# Mainsnode_v2_wifi.net
KiCad netlist of a schematic drawn in EAGLE
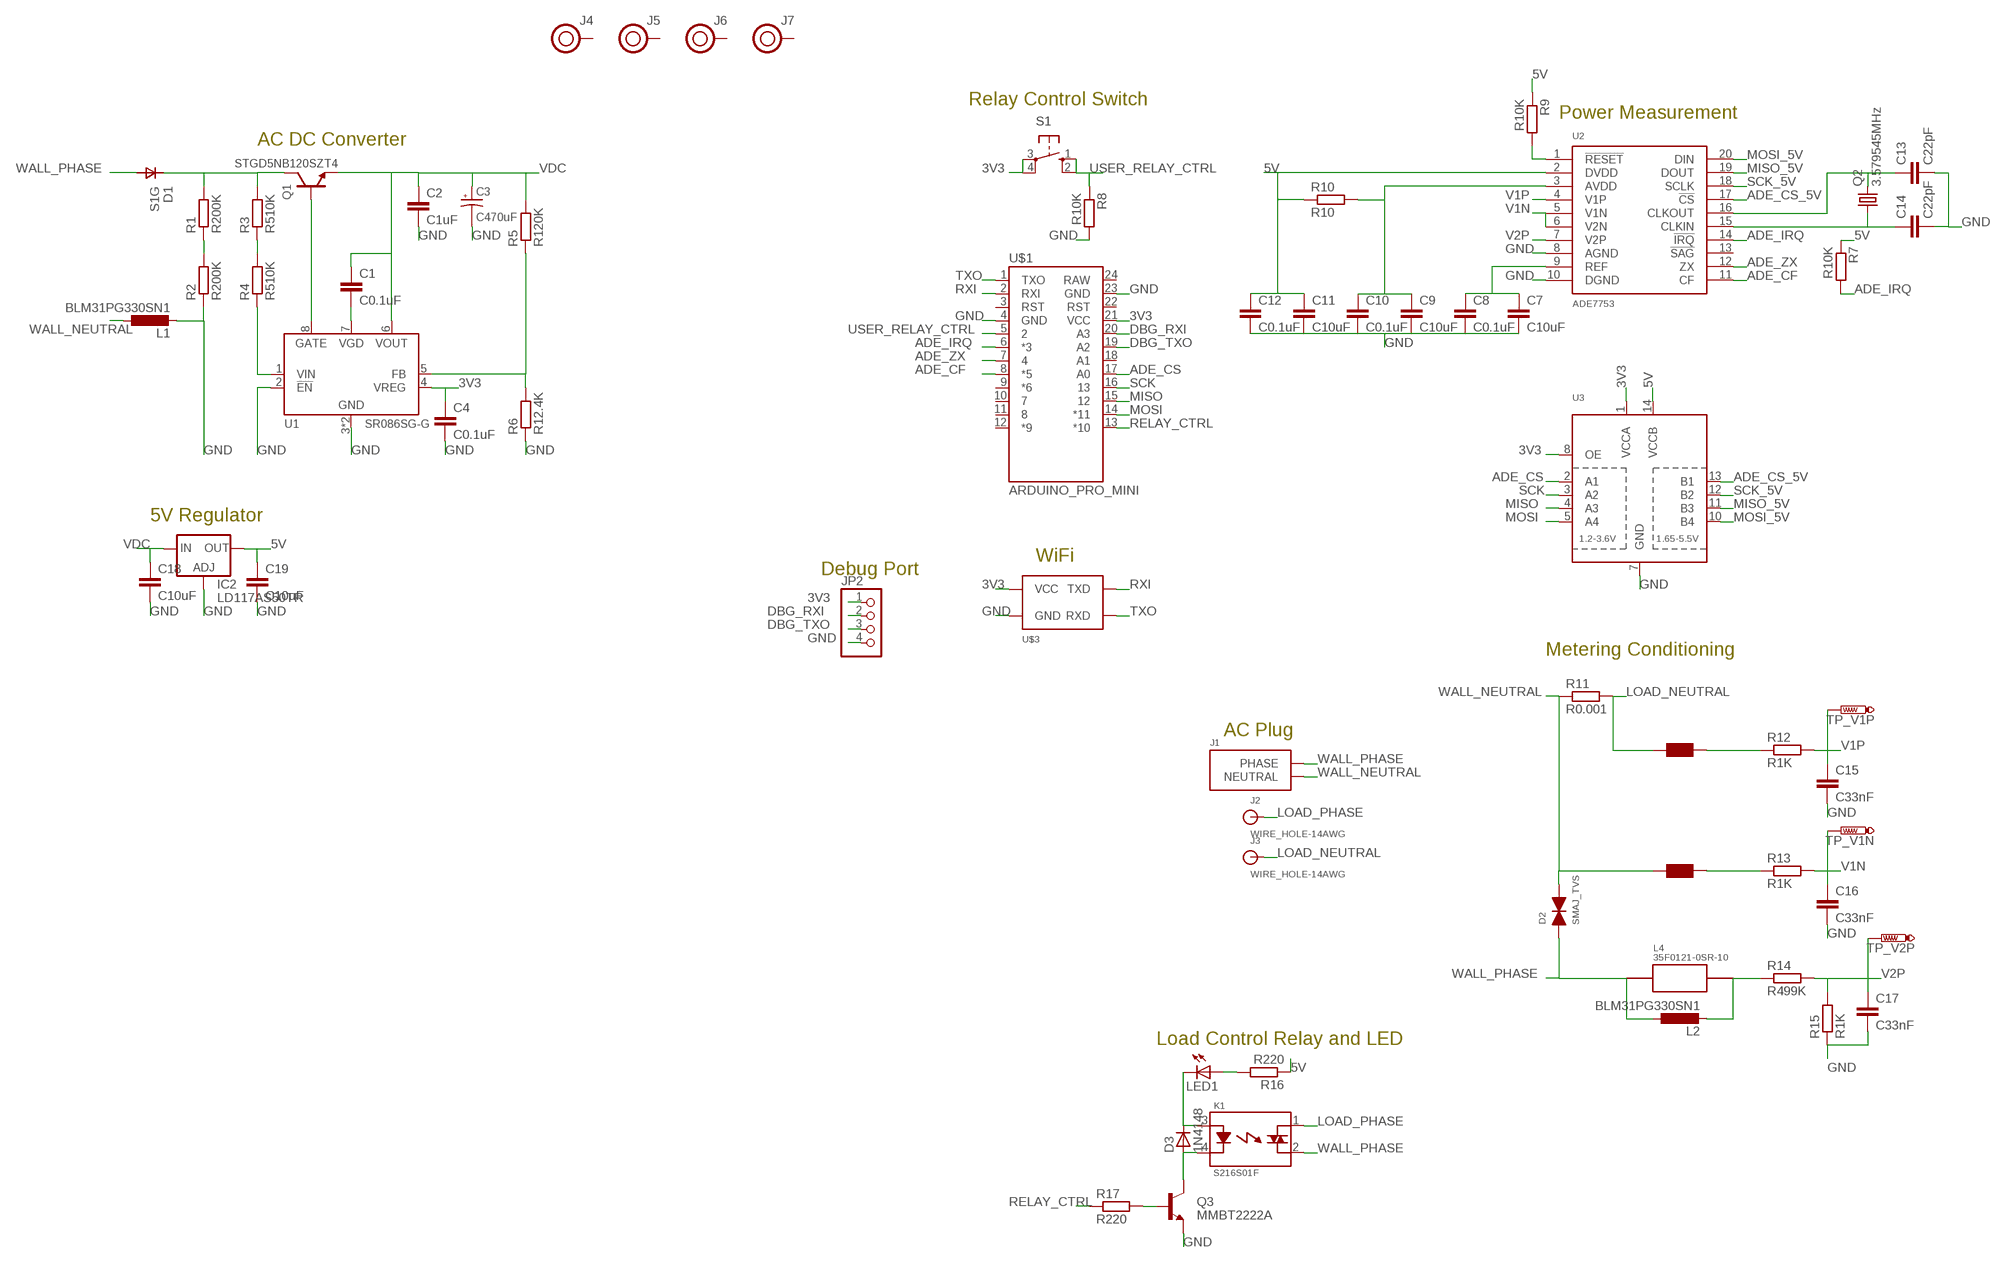
[diagram p0: schematic, sheet 1]

(export (version "E")
  (design (tool "Eeschema 10.0.6"))
  (components
    (comp (ref "C1")
      (value "C0.1uF")
      (footprint "eagle-import:C0805")
      (libsource (lib "eagle-import") (part "C-EUC0805"))
    )
    (comp (ref "C2")
      (value "C1uF")
      (footprint "eagle-import:C0805")
      (libsource (lib "eagle-import") (part "C-EUC0805"))
    )
    (comp (ref "C3")
      (value "C470uF")
      (footprint "eagle-import:CAP_SM_10MM")
      (libsource (lib "eagle-import") (part "CAP_EEE-FP1E471AP"))
    )
    (comp (ref "C4")
      (value "C0.1uF")
      (footprint "eagle-import:C0805")
      (libsource (lib "eagle-import") (part "C-EUC0805"))
    )
    (comp (ref "C7")
      (value "C10uF")
      (footprint "eagle-import:C0805")
      (libsource (lib "eagle-import") (part "C-EUC0805"))
    )
    (comp (ref "C8")
      (value "C0.1uF")
      (footprint "eagle-import:C0805")
      (libsource (lib "eagle-import") (part "C-EUC0805"))
    )
    (comp (ref "C9")
      (value "C10uF")
      (footprint "eagle-import:C0805")
      (libsource (lib "eagle-import") (part "C-EUC0805"))
    )
    (comp (ref "C10")
      (value "C0.1uF")
      (footprint "eagle-import:C0805")
      (libsource (lib "eagle-import") (part "C-EUC0805"))
    )
    (comp (ref "C11")
      (value "C10uF")
      (footprint "eagle-import:C0805")
      (libsource (lib "eagle-import") (part "C-EUC0805"))
    )
    (comp (ref "C12")
      (value "C0.1uF")
      (footprint "eagle-import:C0805")
      (libsource (lib "eagle-import") (part "C-EUC0805"))
    )
    (comp (ref "C13")
      (value "C22pF")
      (footprint "eagle-import:C0805")
      (libsource (lib "eagle-import") (part "C-EUC0805"))
    )
    (comp (ref "C14")
      (value "C22pF")
      (footprint "eagle-import:C0805")
      (libsource (lib "eagle-import") (part "C-EUC0805"))
    )
    (comp (ref "C15")
      (value "C33nF")
      (footprint "eagle-import:C0805")
      (libsource (lib "eagle-import") (part "C-EUC0805"))
    )
    (comp (ref "C16")
      (value "C33nF")
      (footprint "eagle-import:C0805")
      (libsource (lib "eagle-import") (part "C-EUC0805"))
    )
    (comp (ref "C17")
      (value "C33nF")
      (footprint "eagle-import:C0805")
      (libsource (lib "eagle-import") (part "C-EUC0805"))
    )
    (comp (ref "C18")
      (value "C10uF")
      (footprint "eagle-import:C0805")
      (libsource (lib "eagle-import") (part "C-EUC0805"))
    )
    (comp (ref "C19")
      (value "C10uF")
      (footprint "eagle-import:C0805")
      (libsource (lib "eagle-import") (part "C-EUC0805"))
    )
    (comp (ref "D1")
      (value "S1G")
      (footprint "eagle-import:DO-214AC")
      (libsource (lib "eagle-import") (part "S1G"))
    )
    (comp (ref "D2")
      (value "SMAJ_TVS")
      (footprint "eagle-import:DO214_TVS")
      (libsource (lib "eagle-import") (part "SMAJ_TVS"))
    )
    (comp (ref "D3")
      (value "1N4148")
      (footprint "eagle-import:SOD80")
      (libsource (lib "eagle-import") (part "D-SOD-80"))
    )
    (comp (ref "IC2")
      (value "LD117AS50TR")
      (footprint "eagle-import:SOT223")
      (libsource (lib "eagle-import") (part "LD117A?S50TR"))
    )
    (comp (ref "J1")
      (value "AC-PLUG-2")
      (footprint "eagle-import:AC_MALE_PINS_2")
      (libsource (lib "eagle-import") (part "AC-PLUG-2"))
    )
    (comp (ref "J2")
      (value "WIRE_HOLE-14AWG")
      (footprint "eagle-import:WIRE_HOLE-14AWG")
      (libsource (lib "eagle-import") (part "WIRE_HOLE-14AWG"))
    )
    (comp (ref "J3")
      (value "WIRE_HOLE-14AWG")
      (footprint "eagle-import:WIRE_HOLE-14AWG")
      (libsource (lib "eagle-import") (part "WIRE_HOLE-14AWG"))
    )
    (comp (ref "J4")
      (value "HOLE")
      (footprint "eagle-import:HOLE-0.125")
      (libsource (lib "eagle-import") (part "HOLE"))
    )
    (comp (ref "J5")
      (value "HOLE")
      (footprint "eagle-import:HOLE-0.125")
      (libsource (lib "eagle-import") (part "HOLE"))
    )
    (comp (ref "J6")
      (value "HOLE")
      (footprint "eagle-import:HOLE-0.125")
      (libsource (lib "eagle-import") (part "HOLE"))
    )
    (comp (ref "J7")
      (value "HOLE")
      (footprint "eagle-import:HOLE-0.125")
      (libsource (lib "eagle-import") (part "HOLE"))
    )
    (comp (ref "JP2")
      (value "PINHD-1X4")
      (footprint "eagle-import:1X04")
      (libsource (lib "eagle-import") (part "PINHD-1X4"))
    )
    (comp (ref "K1")
      (value "S216S01F")
      (footprint "eagle-import:RELAY_SX16S0X")
      (libsource (lib "eagle-import") (part "S216S01F"))
    )
    (comp (ref "L1")
      (value "BLM31PG330SN1")
      (footprint "eagle-import:L3216C")
      (libsource (lib "eagle-import") (part "L-EUL3216C"))
    )
    (comp (ref "L2")
      (value "BLM31PG330SN1")
      (footprint "eagle-import:L3216C")
      (libsource (lib "eagle-import") (part "L-EUL3216C"))
    )
    (comp (ref "L4")
      (value "35F0121-0SR-10")
      (footprint "eagle-import:35F0102")
      (libsource (lib "eagle-import") (part "35F0121-0SR-10"))
    )
    (comp (ref "LED1")
      (value "LED3MM")
      (footprint "eagle-import:LED3MM")
      (libsource (lib "eagle-import") (part "LED3MM"))
    )
    (comp (ref "Q1")
      (value "STGD5NB120SZT4")
      (footprint "eagle-import:DPAK")
      (libsource (lib "eagle-import") (part "STGD5NB120SZT4"))
    )
    (comp (ref "Q2")
      (value "3.579545MHz")
      (footprint "eagle-import:HC49_S")
      (libsource (lib "eagle-import") (part "CRYSTALHC49S"))
    )
    (comp (ref "Q3")
      (value "MMBT2222A")
      (footprint "eagle-import:SOT23-3")
      (libsource (lib "eagle-import") (part "TRANSISTOR_NPNMMBT2222A"))
    )
    (comp (ref "R1")
      (value "R200K")
      (footprint "eagle-import:M0805")
      (libsource (lib "eagle-import") (part "R-EU_M0805"))
    )
    (comp (ref "R2")
      (value "R200K")
      (footprint "eagle-import:M0805")
      (libsource (lib "eagle-import") (part "R-EU_M0805"))
    )
    (comp (ref "R3")
      (value "R510K")
      (footprint "eagle-import:M0805")
      (libsource (lib "eagle-import") (part "R-EU_M0805"))
    )
    (comp (ref "R4")
      (value "R510K")
      (footprint "eagle-import:M0805")
      (libsource (lib "eagle-import") (part "R-EU_M0805"))
    )
    (comp (ref "R5")
      (value "R120K")
      (footprint "eagle-import:M0805")
      (libsource (lib "eagle-import") (part "R-EU_M0805"))
    )
    (comp (ref "R6")
      (value "R12.4K")
      (footprint "eagle-import:M0805")
      (libsource (lib "eagle-import") (part "R-EU_M0805"))
    )
    (comp (ref "R7")
      (value "R10K")
      (footprint "eagle-import:R0805")
      (libsource (lib "eagle-import") (part "R-EU_R0805"))
    )
    (comp (ref "R8")
      (value "R10K")
      (footprint "eagle-import:R0805")
      (libsource (lib "eagle-import") (part "R-EU_R0805"))
    )
    (comp (ref "R9")
      (value "R10K")
      (footprint "eagle-import:R0805")
      (libsource (lib "eagle-import") (part "R-EU_R0805"))
    )
    (comp (ref "R10")
      (value "R10")
      (footprint "eagle-import:R0805")
      (libsource (lib "eagle-import") (part "R-EU_R0805"))
    )
    (comp (ref "R11")
      (value "R0.001")
      (footprint "eagle-import:R2512")
      (libsource (lib "eagle-import") (part "R-EU_R2512"))
    )
    (comp (ref "R12")
      (value "R1K")
      (footprint "eagle-import:R0805")
      (libsource (lib "eagle-import") (part "R-EU_R0805"))
    )
    (comp (ref "R13")
      (value "R1K")
      (footprint "eagle-import:R0805")
      (libsource (lib "eagle-import") (part "R-EU_R0805"))
    )
    (comp (ref "R14")
      (value "R499K")
      (footprint "eagle-import:R0805")
      (libsource (lib "eagle-import") (part "R-EU_R0805"))
    )
    (comp (ref "R15")
      (value "R1K")
      (footprint "eagle-import:R0805")
      (libsource (lib "eagle-import") (part "R-EU_R0805"))
    )
    (comp (ref "R16")
      (value "R220")
      (footprint "eagle-import:R0805")
      (libsource (lib "eagle-import") (part "R-EU_R0805"))
    )
    (comp (ref "R17")
      (value "R220")
      (footprint "eagle-import:R0805")
      (libsource (lib "eagle-import") (part "R-EU_R0805"))
    )
    (comp (ref "S1")
      (value "10-XX")
      (footprint "eagle-import:B3F-10XX")
      (fields (field (name "MPN") "B3F-1000"))
      (libsource (lib "eagle-import") (part "10-XX"))
    )
    (comp (ref "TP_V1N")
      (value "PTR1PAD1-13")
      (footprint "eagle-import:P1-13")
      (libsource (lib "eagle-import") (part "PTR1PAD1-13"))
    )
    (comp (ref "TP_V1P")
      (value "PTR1PAD1-13")
      (footprint "eagle-import:P1-13")
      (libsource (lib "eagle-import") (part "PTR1PAD1-13"))
    )
    (comp (ref "TP_V2P")
      (value "PTR1PAD1-13")
      (footprint "eagle-import:P1-13")
      (libsource (lib "eagle-import") (part "PTR1PAD1-13"))
    )
    (comp (ref "U$1")
      (value "ARDUINO_PRO_MINI")
      (footprint "eagle-import:ARDUINO_PRO_MINI")
      (libsource (lib "eagle-import") (part "ARDUINO_PRO_MINI"))
    )
    (comp (ref "U$3")
      (value "ESP8266")
      (footprint "eagle-import:ESP8266")
      (libsource (lib "eagle-import") (part "ESP8266"))
    )
    (comp (ref "U$4")
      (value "BLM18BB151SN1")
      (footprint "eagle-import:L0603")
      (libsource (lib "eagle-import") (part "L0603"))
    )
    (comp (ref "U$5")
      (value "BLM18BB151SN1")
      (footprint "eagle-import:L0603")
      (libsource (lib "eagle-import") (part "L0603"))
    )
    (comp (ref "U1")
      (value "SR086SG-G")
      (footprint "eagle-import:SR086")
      (libsource (lib "eagle-import") (part "SR086SG-G"))
    )
    (comp (ref "U2")
      (value "ADE7753")
      (footprint "eagle-import:SSOP-20")
      (libsource (lib "eagle-import") (part "ADE7753"))
    )
    (comp (ref "U3")
      (value "TXB0104PWR")
      (footprint "eagle-import:TSSOP14")
      (libsource (lib "eagle-import") (part "TXB0104PWR"))
    )
  )
  (nets
    (net (code "1") (name "/3V3") (class "Default")
      (node (ref "C4") (pin "1") (pinfunction "1_1") (pintype "passive"))
      (node (ref "JP2") (pin "1") (pinfunction "1_1") (pintype "passive"))
      (node (ref "S1") (pin "3") (pinfunction "P_3") (pintype "passive"))
      (node (ref "S1") (pin "4") (pinfunction "P1_4") (pintype "passive"))
      (node (ref "U$1") (pin "21") (pinfunction "VCC_21") (pintype "bidirectional"))
      (node (ref "U$3") (pin "VCC") (pinfunction "VCC_VCC") (pintype "bidirectional"))
      (node (ref "U1") (pin "4") (pinfunction "VREG_4") (pintype "bidirectional"))
      (node (ref "U3") (pin "1") (pinfunction "VCCA_1") (pintype "bidirectional"))
      (node (ref "U3") (pin "8") (pinfunction "OE_8") (pintype "bidirectional"))
    )
    (net (code "2") (name "/5V") (class "Default")
      (node (ref "C11") (pin "1") (pinfunction "1_1") (pintype "passive"))
      (node (ref "C12") (pin "1") (pinfunction "1_1") (pintype "passive"))
      (node (ref "C19") (pin "1") (pinfunction "1_1") (pintype "passive"))
      (node (ref "IC2") (pin "4") (pinfunction "OUT_4") (pintype "passive"))
      (node (ref "R10") (pin "1") (pinfunction "1_1") (pintype "passive"))
      (node (ref "R16") (pin "1") (pinfunction "1_1") (pintype "passive"))
      (node (ref "R7") (pin "1") (pinfunction "1_1") (pintype "passive"))
      (node (ref "R9") (pin "1") (pinfunction "1_1") (pintype "passive"))
      (node (ref "U2") (pin "2") (pinfunction "DVDD_2") (pintype "bidirectional"))
      (node (ref "U3") (pin "14") (pinfunction "VCCB_14") (pintype "bidirectional"))
    )
    (net (code "3") (name "/ADE_CF") (class "Default")
      (node (ref "U$1") (pin "8") (pinfunction "*5_8") (pintype "bidirectional"))
      (node (ref "U2") (pin "11") (pinfunction "CF_11") (pintype "bidirectional"))
    )
    (net (code "4") (name "/ADE_CS") (class "Default")
      (node (ref "U$1") (pin "17") (pinfunction "A0_17") (pintype "bidirectional"))
      (node (ref "U3") (pin "2") (pinfunction "A1_2") (pintype "bidirectional"))
    )
    (net (code "5") (name "/ADE_CS_5V") (class "Default")
      (node (ref "U2") (pin "17") (pinfunction "~{CS}_17") (pintype "bidirectional"))
      (node (ref "U3") (pin "13") (pinfunction "B1_13") (pintype "bidirectional"))
    )
    (net (code "6") (name "/ADE_IRQ") (class "Default")
      (node (ref "R7") (pin "2") (pinfunction "2_2") (pintype "passive"))
      (node (ref "U$1") (pin "6") (pinfunction "*3_6") (pintype "bidirectional"))
      (node (ref "U2") (pin "14") (pinfunction "~{IRQ}_14") (pintype "bidirectional"))
    )
    (net (code "7") (name "/ADE_ZX") (class "Default")
      (node (ref "U$1") (pin "7") (pinfunction "4_7") (pintype "bidirectional"))
      (node (ref "U2") (pin "12") (pinfunction "ZX_12") (pintype "bidirectional"))
    )
    (net (code "8") (name "/DBG_RXI") (class "Default")
      (node (ref "JP2") (pin "2") (pinfunction "2_2") (pintype "passive"))
      (node (ref "U$1") (pin "20") (pinfunction "A3_20") (pintype "bidirectional"))
    )
    (net (code "9") (name "/DBG_TXO") (class "Default")
      (node (ref "JP2") (pin "3") (pinfunction "3_3") (pintype "passive"))
      (node (ref "U$1") (pin "19") (pinfunction "A2_19") (pintype "bidirectional"))
    )
    (net (code "10") (name "/GND") (class "Default")
      (node (ref "C10") (pin "2") (pinfunction "2_2") (pintype "passive"))
      (node (ref "C11") (pin "2") (pinfunction "2_2") (pintype "passive"))
      (node (ref "C12") (pin "2") (pinfunction "2_2") (pintype "passive"))
      (node (ref "C13") (pin "2") (pinfunction "2_2") (pintype "passive"))
      (node (ref "C14") (pin "2") (pinfunction "2_2") (pintype "passive"))
      (node (ref "C15") (pin "2") (pinfunction "2_2") (pintype "passive"))
      (node (ref "C16") (pin "2") (pinfunction "2_2") (pintype "passive"))
      (node (ref "C17") (pin "2") (pinfunction "2_2") (pintype "passive"))
      (node (ref "C18") (pin "2") (pinfunction "2_2") (pintype "passive"))
      (node (ref "C19") (pin "2") (pinfunction "2_2") (pintype "passive"))
      (node (ref "C2") (pin "2") (pinfunction "2_2") (pintype "passive"))
      (node (ref "C3") (pin "-") (pinfunction "-_-") (pintype "bidirectional"))
      (node (ref "C4") (pin "2") (pinfunction "2_2") (pintype "passive"))
      (node (ref "C7") (pin "2") (pinfunction "2_2") (pintype "passive"))
      (node (ref "C8") (pin "2") (pinfunction "2_2") (pintype "passive"))
      (node (ref "C9") (pin "2") (pinfunction "2_2") (pintype "passive"))
      (node (ref "IC2") (pin "1") (pinfunction "ADJ_1") (pintype "input"))
      (node (ref "JP2") (pin "4") (pinfunction "4_4") (pintype "passive"))
      (node (ref "L1") (pin "2") (pinfunction "2_2") (pintype "passive"))
      (node (ref "Q3") (pin "2") (pinfunction "E_2") (pintype "passive"))
      (node (ref "R15") (pin "1") (pinfunction "1_1") (pintype "passive"))
      (node (ref "R2") (pin "1") (pinfunction "1_1") (pintype "passive"))
      (node (ref "R6") (pin "1") (pinfunction "1_1") (pintype "passive"))
      (node (ref "R8") (pin "2") (pinfunction "2_2") (pintype "passive"))
      (node (ref "U$1") (pin "23") (pinfunction "GND_23") (pintype "bidirectional"))
      (node (ref "U$1") (pin "4") (pinfunction "GND_4") (pintype "bidirectional"))
      (node (ref "U$3") (pin "GND") (pinfunction "GND_GND") (pintype "bidirectional"))
      (node (ref "U1") (pin "2") (pinfunction "~{EN}_2") (pintype "bidirectional"))
      (node (ref "U1") (pin "3") (pinfunction "GND_3") (pintype "bidirectional"))
      (node (ref "U1") (pin "PAD") (pinfunction "GND_PAD") (pintype "bidirectional"))
      (node (ref "U2") (pin "10") (pinfunction "DGND_10") (pintype "bidirectional"))
      (node (ref "U2") (pin "8") (pinfunction "AGND_8") (pintype "bidirectional"))
      (node (ref "U3") (pin "7") (pinfunction "GND_7") (pintype "bidirectional"))
    )
    (net (code "11") (name "/LOAD_NEUTRAL") (class "Default")
      (node (ref "J3") (pin "P$1") (pinfunction "P$1_P$1") (pintype "bidirectional"))
      (node (ref "R11") (pin "2") (pinfunction "2_2") (pintype "passive"))
      (node (ref "U$4") (pin "1") (pinfunction "P$1_1") (pintype "bidirectional"))
    )
    (net (code "12") (name "/LOAD_PHASE") (class "Default")
      (node (ref "J2") (pin "P$1") (pinfunction "P$1_P$1") (pintype "bidirectional"))
      (node (ref "K1") (pin "1") (pinfunction "1_1") (pintype "bidirectional"))
    )
    (net (code "13") (name "/MISO") (class "Default")
      (node (ref "U$1") (pin "15") (pinfunction "12_15") (pintype "bidirectional"))
      (node (ref "U3") (pin "4") (pinfunction "A3_4") (pintype "bidirectional"))
    )
    (net (code "14") (name "/MISO_5V") (class "Default")
      (node (ref "U2") (pin "19") (pinfunction "DOUT_19") (pintype "bidirectional"))
      (node (ref "U3") (pin "11") (pinfunction "B3_11") (pintype "bidirectional"))
    )
    (net (code "15") (name "/MOSI") (class "Default")
      (node (ref "U$1") (pin "14") (pinfunction "*11_14") (pintype "bidirectional"))
      (node (ref "U3") (pin "5") (pinfunction "A4_5") (pintype "bidirectional"))
    )
    (net (code "16") (name "/MOSI_5V") (class "Default")
      (node (ref "U2") (pin "20") (pinfunction "DIN_20") (pintype "bidirectional"))
      (node (ref "U3") (pin "10") (pinfunction "B4_10") (pintype "bidirectional"))
    )
    (net (code "17") (name "/RELAY_CTRL") (class "Default")
      (node (ref "R17") (pin "1") (pinfunction "1_1") (pintype "passive"))
      (node (ref "U$1") (pin "13") (pinfunction "*10_13") (pintype "bidirectional"))
    )
    (net (code "18") (name "/RXI") (class "Default")
      (node (ref "U$1") (pin "2") (pinfunction "RXI_2") (pintype "bidirectional"))
      (node (ref "U$3") (pin "TXD") (pinfunction "TXD_TXD") (pintype "bidirectional"))
    )
    (net (code "19") (name "/SCK") (class "Default")
      (node (ref "U$1") (pin "16") (pinfunction "13_16") (pintype "bidirectional"))
      (node (ref "U3") (pin "3") (pinfunction "A2_3") (pintype "bidirectional"))
    )
    (net (code "20") (name "/SCK_5V") (class "Default")
      (node (ref "U2") (pin "18") (pinfunction "SCLK_18") (pintype "bidirectional"))
      (node (ref "U3") (pin "12") (pinfunction "B2_12") (pintype "bidirectional"))
    )
    (net (code "21") (name "/TXO") (class "Default")
      (node (ref "U$1") (pin "1") (pinfunction "TXO_1") (pintype "bidirectional"))
      (node (ref "U$3") (pin "RXD") (pinfunction "RXD_RXD") (pintype "bidirectional"))
    )
    (net (code "22") (name "/USER_RELAY_CTRL") (class "Default")
      (node (ref "R8") (pin "1") (pinfunction "1_1") (pintype "passive"))
      (node (ref "S1") (pin "1") (pinfunction "S_1") (pintype "passive"))
      (node (ref "S1") (pin "2") (pinfunction "S1_2") (pintype "passive"))
      (node (ref "U$1") (pin "5") (pinfunction "2_5") (pintype "bidirectional"))
    )
    (net (code "23") (name "/V1N") (class "Default")
      (node (ref "C16") (pin "1") (pinfunction "1_1") (pintype "passive"))
      (node (ref "R13") (pin "2") (pinfunction "2_2") (pintype "passive"))
      (node (ref "TP_V1N") (pin "TP") (pinfunction "TP_TP") (pintype "input"))
      (node (ref "U2") (pin "5") (pinfunction "V1N_5") (pintype "bidirectional"))
      (node (ref "U2") (pin "6") (pinfunction "V2N_6") (pintype "bidirectional"))
    )
    (net (code "24") (name "/V1P") (class "Default")
      (node (ref "C15") (pin "1") (pinfunction "1_1") (pintype "passive"))
      (node (ref "R12") (pin "2") (pinfunction "2_2") (pintype "passive"))
      (node (ref "TP_V1P") (pin "TP") (pinfunction "TP_TP") (pintype "input"))
      (node (ref "U2") (pin "4") (pinfunction "V1P_4") (pintype "bidirectional"))
    )
    (net (code "25") (name "/V2P") (class "Default")
      (node (ref "C17") (pin "1") (pinfunction "1_1") (pintype "passive"))
      (node (ref "R14") (pin "2") (pinfunction "2_2") (pintype "passive"))
      (node (ref "R15") (pin "2") (pinfunction "2_2") (pintype "passive"))
      (node (ref "TP_V2P") (pin "TP") (pinfunction "TP_TP") (pintype "input"))
      (node (ref "U2") (pin "7") (pinfunction "V2P_7") (pintype "bidirectional"))
    )
    (net (code "26") (name "/VDC") (class "Default")
      (node (ref "C1") (pin "1") (pinfunction "1_1") (pintype "passive"))
      (node (ref "C18") (pin "1") (pinfunction "1_1") (pintype "passive"))
      (node (ref "C2") (pin "1") (pinfunction "1_1") (pintype "passive"))
      (node (ref "C3") (pin "+") (pinfunction "+_+") (pintype "bidirectional"))
      (node (ref "IC2") (pin "3") (pinfunction "IN_3") (pintype "input"))
      (node (ref "Q1") (pin "P$3") (pinfunction "E_P$3") (pintype "bidirectional"))
      (node (ref "R5") (pin "2") (pinfunction "2_2") (pintype "passive"))
      (node (ref "U1") (pin "6") (pinfunction "VOUT_6") (pintype "bidirectional"))
    )
    (net (code "27") (name "/WALL_NEUTRAL") (class "Default")
      (node (ref "D2") (pin "CATHODE") (pinfunction "P$2_CATHODE") (pintype "bidirectional"))
      (node (ref "J1") (pin "NEUTRAL1") (pinfunction "NEUTRAL_NEUTRAL1") (pintype "bidirectional"))
      (node (ref "J1") (pin "NEUTRAL2") (pinfunction "NEUTRAL_NEUTRAL2") (pintype "bidirectional"))
      (node (ref "L1") (pin "1") (pinfunction "1_1") (pintype "passive"))
      (node (ref "R11") (pin "1") (pinfunction "1_1") (pintype "passive"))
      (node (ref "U$5") (pin "1") (pinfunction "P$1_1") (pintype "bidirectional"))
    )
    (net (code "28") (name "/WALL_PHASE") (class "Default")
      (node (ref "D1") (pin "ANNODE") (pinfunction "ANNODE_ANNODE") (pintype "bidirectional"))
      (node (ref "D2") (pin "ANODE") (pinfunction "P$1_ANODE") (pintype "bidirectional"))
      (node (ref "J1") (pin "PHASE1") (pinfunction "PHASE_PHASE1") (pintype "bidirectional"))
      (node (ref "J1") (pin "PHASE2") (pinfunction "PHASE_PHASE2") (pintype "bidirectional"))
      (node (ref "K1") (pin "2") (pinfunction "2_2") (pintype "bidirectional"))
      (node (ref "L2") (pin "1") (pinfunction "1_1") (pintype "passive"))
      (node (ref "L4") (pin "1") (pinfunction "P$1_1") (pintype "bidirectional"))
    )
    (net (code "29") (name "Net-(D3-A)") (class "Default")
      (node (ref "D3") (pin "2") (pinfunction "A_2") (pintype "passive"))
      (node (ref "K1") (pin "4") (pinfunction "4_4") (pintype "bidirectional"))
      (node (ref "Q3") (pin "3") (pinfunction "C_3") (pintype "passive"))
    )
    (net (code "30") (name "Net-(D3-C)") (class "Default")
      (node (ref "D3") (pin "1") (pinfunction "C_1") (pintype "passive"))
      (node (ref "K1") (pin "3") (pinfunction "3_3") (pintype "bidirectional"))
      (node (ref "LED1") (pin "K") (pinfunction "C_K") (pintype "passive"))
    )
    (net (code "31") (name "Net-(L4-P$2)") (class "Default")
      (node (ref "L2") (pin "2") (pinfunction "2_2") (pintype "passive"))
      (node (ref "L4") (pin "2") (pinfunction "P$2_2") (pintype "bidirectional"))
      (node (ref "R14") (pin "1") (pinfunction "1_1") (pintype "passive"))
    )
    (net (code "32") (name "Net-(LED1-PadA)") (class "Default")
      (node (ref "LED1") (pin "A") (pinfunction "A_A") (pintype "passive"))
      (node (ref "R16") (pin "2") (pinfunction "2_2") (pintype "passive"))
    )
    (net (code "33") (name "Net-(Q1-C)") (class "Default")
      (node (ref "D1") (pin "CATHODE") (pinfunction "CATHODE_CATHODE") (pintype "bidirectional"))
      (node (ref "Q1") (pin "P$2") (pinfunction "C_P$2") (pintype "bidirectional"))
      (node (ref "R1") (pin "2") (pinfunction "2_2") (pintype "passive"))
      (node (ref "R3") (pin "2") (pinfunction "2_2") (pintype "passive"))
    )
    (net (code "34") (name "Net-(Q1-G)") (class "Default")
      (node (ref "Q1") (pin "P$1") (pinfunction "G_P$1") (pintype "bidirectional"))
      (node (ref "U1") (pin "8") (pinfunction "GATE_8") (pintype "bidirectional"))
    )
    (net (code "35") (name "Net-(Q3-B)") (class "Default")
      (node (ref "Q3") (pin "1") (pinfunction "B_1") (pintype "passive"))
      (node (ref "R17") (pin "2") (pinfunction "2_2") (pintype "passive"))
    )
    (net (code "36") (name "Net-(R1-Pad1)") (class "Default")
      (node (ref "R1") (pin "1") (pinfunction "1_1") (pintype "passive"))
      (node (ref "R2") (pin "2") (pinfunction "2_2") (pintype "passive"))
    )
    (net (code "37") (name "Net-(R3-Pad1)") (class "Default")
      (node (ref "R3") (pin "1") (pinfunction "1_1") (pintype "passive"))
      (node (ref "R4") (pin "2") (pinfunction "2_2") (pintype "passive"))
    )
    (net (code "38") (name "Net-(U$4-P$2)") (class "Default")
      (node (ref "R12") (pin "1") (pinfunction "1_1") (pintype "passive"))
      (node (ref "U$4") (pin "2") (pinfunction "P$2_2") (pintype "bidirectional"))
    )
    (net (code "39") (name "Net-(U$5-P$2)") (class "Default")
      (node (ref "R13") (pin "1") (pinfunction "1_1") (pintype "passive"))
      (node (ref "U$5") (pin "2") (pinfunction "P$2_2") (pintype "bidirectional"))
    )
    (net (code "40") (name "Net-(U1-FB)") (class "Default")
      (node (ref "R5") (pin "1") (pinfunction "1_1") (pintype "passive"))
      (node (ref "R6") (pin "2") (pinfunction "2_2") (pintype "passive"))
      (node (ref "U1") (pin "5") (pinfunction "FB_5") (pintype "bidirectional"))
    )
    (net (code "41") (name "Net-(U1-VGD)") (class "Default")
      (node (ref "C1") (pin "2") (pinfunction "2_2") (pintype "passive"))
      (node (ref "U1") (pin "7") (pinfunction "VGD_7") (pintype "bidirectional"))
    )
    (net (code "42") (name "Net-(U1-VIN)") (class "Default")
      (node (ref "R4") (pin "1") (pinfunction "1_1") (pintype "passive"))
      (node (ref "U1") (pin "1") (pinfunction "VIN_1") (pintype "bidirectional"))
    )
    (net (code "43") (name "Net-(U2-AVDD)") (class "Default")
      (node (ref "C10") (pin "1") (pinfunction "1_1") (pintype "passive"))
      (node (ref "C9") (pin "1") (pinfunction "1_1") (pintype "passive"))
      (node (ref "R10") (pin "2") (pinfunction "2_2") (pintype "passive"))
      (node (ref "U2") (pin "3") (pinfunction "AVDD_3") (pintype "bidirectional"))
    )
    (net (code "44") (name "Net-(U2-CLKIN)") (class "Default")
      (node (ref "C14") (pin "1") (pinfunction "1_1") (pintype "passive"))
      (node (ref "Q2") (pin "1") (pinfunction "1_1") (pintype "passive"))
      (node (ref "U2") (pin "15") (pinfunction "CLKIN_15") (pintype "bidirectional"))
    )
    (net (code "45") (name "Net-(U2-CLKOUT)") (class "Default")
      (node (ref "C13") (pin "1") (pinfunction "1_1") (pintype "passive"))
      (node (ref "Q2") (pin "2") (pinfunction "2_2") (pintype "passive"))
      (node (ref "U2") (pin "16") (pinfunction "CLKOUT_16") (pintype "bidirectional"))
    )
    (net (code "46") (name "Net-(U2-REF)") (class "Default")
      (node (ref "C7") (pin "1") (pinfunction "1_1") (pintype "passive"))
      (node (ref "C8") (pin "1") (pinfunction "1_1") (pintype "passive"))
      (node (ref "U2") (pin "9") (pinfunction "REF_9") (pintype "bidirectional"))
    )
    (net (code "47") (name "Net-(U2-~{RESET})") (class "Default")
      (node (ref "R9") (pin "2") (pinfunction "2_2") (pintype "passive"))
      (node (ref "U2") (pin "1") (pinfunction "~{RESET}_1") (pintype "bidirectional"))
    )
    (net (code "48") (name "unconnected-(J4-P$1-Pad1)") (class "Default")
      (node (ref "J4") (pin "1") (pinfunction "P$1_1") (pintype "bidirectional"))
    )
    (net (code "49") (name "unconnected-(J5-P$1-Pad1)") (class "Default")
      (node (ref "J5") (pin "1") (pinfunction "P$1_1") (pintype "bidirectional"))
    )
    (net (code "50") (name "unconnected-(J6-P$1-Pad1)") (class "Default")
      (node (ref "J6") (pin "1") (pinfunction "P$1_1") (pintype "bidirectional"))
    )
    (net (code "51") (name "unconnected-(J7-P$1-Pad1)") (class "Default")
      (node (ref "J7") (pin "1") (pinfunction "P$1_1") (pintype "bidirectional"))
    )
    (net (code "52") (name "unconnected-(U$1-*6-Pad9)") (class "Default")
      (node (ref "U$1") (pin "9") (pinfunction "*6_9") (pintype "bidirectional"))
    )
    (net (code "53") (name "unconnected-(U$1-*9-Pad12)") (class "Default")
      (node (ref "U$1") (pin "12") (pinfunction "*9_12") (pintype "bidirectional"))
    )
    (net (code "54") (name "unconnected-(U$1-7-Pad10)") (class "Default")
      (node (ref "U$1") (pin "10") (pinfunction "7_10") (pintype "bidirectional"))
    )
    (net (code "55") (name "unconnected-(U$1-8-Pad11)") (class "Default")
      (node (ref "U$1") (pin "11") (pinfunction "8_11") (pintype "bidirectional"))
    )
    (net (code "56") (name "unconnected-(U$1-A1-Pad18)") (class "Default")
      (node (ref "U$1") (pin "18") (pinfunction "A1_18") (pintype "bidirectional"))
    )
    (net (code "57") (name "unconnected-(U$1-RAW-Pad24)") (class "Default")
      (node (ref "U$1") (pin "24") (pinfunction "RAW_24") (pintype "bidirectional"))
    )
    (net (code "58") (name "unconnected-(U$1-RST-Pad3)") (class "Default")
      (node (ref "U$1") (pin "3") (pinfunction "RST_3") (pintype "bidirectional"))
    )
    (net (code "59") (name "unconnected-(U$1-RST-Pad22)") (class "Default")
      (node (ref "U$1") (pin "22") (pinfunction "RST_22") (pintype "bidirectional"))
    )
    (net (code "60") (name "unconnected-(U2-~{SAG}-Pad13)") (class "Default")
      (node (ref "U2") (pin "13") (pinfunction "~{SAG}_13") (pintype "bidirectional"))
    )
  )
)
